# lcd_booster_mk2.net
KiCad netlist of a schematic drawn in EAGLE
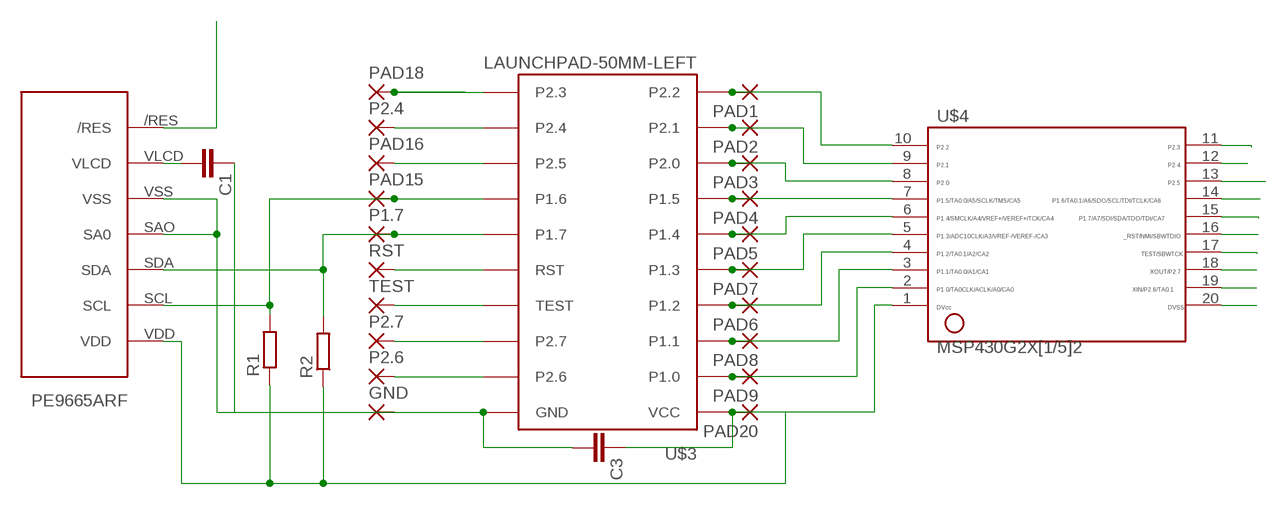
[diagram p0: schematic, sheet 1]

(export (version "E")
  (design (tool "Eeschema 10.0.6"))
  (components
    (comp (ref "C1")
      (value "C-EUC1206")
      (footprint "eagle-import:C1206")
      (libsource (lib "eagle-import") (part "C-EUC1206"))
    )
    (comp (ref "C3")
      (value "C-EUC1206")
      (footprint "eagle-import:C1206")
      (libsource (lib "eagle-import") (part "C-EUC1206"))
    )
    (comp (ref "GND")
      (value "1,6/0,9")
      (footprint "eagle-import:1,6_0,9")
      (libsource (lib "eagle-import") (part "1,6/0,9"))
    )
    (comp (ref "P1.7")
      (value "1,6/0,9")
      (footprint "eagle-import:1,6_0,9")
      (libsource (lib "eagle-import") (part "1,6/0,9"))
    )
    (comp (ref "P2.4")
      (value "1,6/0,9")
      (footprint "eagle-import:1,6_0,9")
      (libsource (lib "eagle-import") (part "1,6/0,9"))
    )
    (comp (ref "P2.6")
      (value "1,6/0,9")
      (footprint "eagle-import:1,6_0,9")
      (libsource (lib "eagle-import") (part "1,6/0,9"))
    )
    (comp (ref "P2.7")
      (value "1,6/0,9")
      (footprint "eagle-import:1,6_0,9")
      (libsource (lib "eagle-import") (part "1,6/0,9"))
    )
    (comp (ref "PAD1")
      (value "1,6/0,9")
      (footprint "eagle-import:1,6_0,9")
      (libsource (lib "eagle-import") (part "1,6/0,9"))
    )
    (comp (ref "PAD2")
      (value "1,6/0,9")
      (footprint "eagle-import:1,6_0,9")
      (libsource (lib "eagle-import") (part "1,6/0,9"))
    )
    (comp (ref "PAD3")
      (value "1,6/0,9")
      (footprint "eagle-import:1,6_0,9")
      (libsource (lib "eagle-import") (part "1,6/0,9"))
    )
    (comp (ref "PAD4")
      (value "1,6/0,9")
      (footprint "eagle-import:1,6_0,9")
      (libsource (lib "eagle-import") (part "1,6/0,9"))
    )
    (comp (ref "PAD5")
      (value "1,6/0,9")
      (footprint "eagle-import:1,6_0,9")
      (libsource (lib "eagle-import") (part "1,6/0,9"))
    )
    (comp (ref "PAD6")
      (value "1,6/0,9")
      (footprint "eagle-import:1,6_0,9")
      (libsource (lib "eagle-import") (part "1,6/0,9"))
    )
    (comp (ref "PAD7")
      (value "1,6/0,9")
      (footprint "eagle-import:1,6_0,9")
      (libsource (lib "eagle-import") (part "1,6/0,9"))
    )
    (comp (ref "PAD8")
      (value "1,6/0,9")
      (footprint "eagle-import:1,6_0,9")
      (libsource (lib "eagle-import") (part "1,6/0,9"))
    )
    (comp (ref "PAD9")
      (value "1,6/0,9")
      (footprint "eagle-import:1,6_0,9")
      (libsource (lib "eagle-import") (part "1,6/0,9"))
    )
    (comp (ref "PAD15")
      (value "1,6/0,9")
      (footprint "eagle-import:1,6_0,9")
      (libsource (lib "eagle-import") (part "1,6/0,9"))
    )
    (comp (ref "PAD16")
      (value "1,6/0,9")
      (footprint "eagle-import:1,6_0,9")
      (libsource (lib "eagle-import") (part "1,6/0,9"))
    )
    (comp (ref "PAD18")
      (value "1,6/0,9")
      (footprint "eagle-import:1,6_0,9")
      (libsource (lib "eagle-import") (part "1,6/0,9"))
    )
    (comp (ref "PAD20")
      (value "1,6/0,9")
      (footprint "eagle-import:1,6_0,9")
      (libsource (lib "eagle-import") (part "1,6/0,9"))
    )
    (comp (ref "R1")
      (value "R-EU_M1206")
      (footprint "eagle-import:M1206")
      (libsource (lib "eagle-import") (part "R-EU_M1206"))
    )
    (comp (ref "R2")
      (value "R-EU_M1206")
      (footprint "eagle-import:M1206")
      (libsource (lib "eagle-import") (part "R-EU_M1206"))
    )
    (comp (ref "RST")
      (value "1,6/0,9")
      (footprint "eagle-import:1,6_0,9")
      (libsource (lib "eagle-import") (part "1,6/0,9"))
    )
    (comp (ref "TEST")
      (value "1,6/0,9")
      (footprint "eagle-import:1,6_0,9")
      (libsource (lib "eagle-import") (part "1,6/0,9"))
    )
    (comp (ref "U$2")
      (value "PE9665ARF")
      (footprint "eagle-import:PE9665ARF")
      (libsource (lib "eagle-import") (part "PE9665ARF"))
    )
    (comp (ref "U$3")
      (value "LAUNCHPAD-50MM-LEFT")
      (footprint "eagle-import:LAUNCHPAD-50MM-LEFT")
      (libsource (lib "eagle-import") (part "LAUNCHPAD-50MM-LEFT"))
    )
    (comp (ref "U$4")
      (value "G2X[1/5]2---PW20")
      (footprint "eagle-import:PW20")
      (libsource (lib "eagle-import") (part "G2X[1/5]2---PW20"))
    )
  )
  (nets
    (net (code "1") (name "/GND") (class "Default")
      (node (ref "C1") (pin "1") (pinfunction "1_1") (pintype "passive"))
      (node (ref "C3") (pin "2") (pinfunction "2_2") (pintype "passive"))
      (node (ref "GND") (pin "1") (pinfunction "P_1") (pintype "passive"))
      (node (ref "U$2") (pin "SAO") (pinfunction "SA0_SAO") (pintype "bidirectional"))
      (node (ref "U$2") (pin "VSS") (pinfunction "VSS_VSS") (pintype "power_in"))
      (node (ref "U$3") (pin "GND") (pinfunction "GND_GND") (pintype "power_in"))
      (node (ref "U$4") (pin "20") (pinfunction "20_20") (pintype "bidirectional"))
    )
    (net (code "2") (name "/P1.6") (class "Default")
      (node (ref "PAD15") (pin "1") (pinfunction "P_1") (pintype "passive"))
      (node (ref "R1") (pin "2") (pinfunction "2_2") (pintype "passive"))
      (node (ref "U$2") (pin "SCL") (pinfunction "SCL_SCL") (pintype "bidirectional"))
      (node (ref "U$3") (pin "P1.6") (pinfunction "P1.6_P1.6") (pintype "bidirectional"))
      (node (ref "U$4") (pin "14") (pinfunction "14_14") (pintype "bidirectional"))
    )
    (net (code "3") (name "/P1.7") (class "Default")
      (node (ref "P1.7") (pin "1") (pinfunction "P_1") (pintype "passive"))
      (node (ref "R2") (pin "2") (pinfunction "2_2") (pintype "passive"))
      (node (ref "U$2") (pin "SDA") (pinfunction "SDA_SDA") (pintype "bidirectional"))
      (node (ref "U$3") (pin "P1.7") (pinfunction "P1.7_P1.7") (pintype "bidirectional"))
      (node (ref "U$4") (pin "15") (pinfunction "15_15") (pintype "bidirectional"))
    )
    (net (code "4") (name "/P2.3") (class "Default")
      (node (ref "PAD18") (pin "1") (pinfunction "P_1") (pintype "passive"))
      (node (ref "U$3") (pin "P2.3") (pinfunction "P2.3_P2.3") (pintype "bidirectional"))
      (node (ref "U$4") (pin "11") (pinfunction "11_11") (pintype "bidirectional"))
    )
    (net (code "5") (name "/P2.4") (class "Default")
      (node (ref "P2.4") (pin "1") (pinfunction "P_1") (pintype "passive"))
      (node (ref "U$3") (pin "P2.4") (pinfunction "P2.4_P2.4") (pintype "bidirectional"))
      (node (ref "U$4") (pin "12") (pinfunction "12_12") (pintype "bidirectional"))
    )
    (net (code "6") (name "/P2.5") (class "Default")
      (node (ref "PAD16") (pin "1") (pinfunction "P_1") (pintype "passive"))
      (node (ref "U$3") (pin "P2.5") (pinfunction "P2.5_P2.5") (pintype "bidirectional"))
      (node (ref "U$4") (pin "13") (pinfunction "13_13") (pintype "bidirectional"))
    )
    (net (code "7") (name "/P2.6") (class "Default")
      (node (ref "P2.6") (pin "1") (pinfunction "P_1") (pintype "passive"))
      (node (ref "U$3") (pin "P2.6") (pinfunction "P2.6_P2.6") (pintype "bidirectional"))
      (node (ref "U$4") (pin "19") (pinfunction "19_19") (pintype "bidirectional"))
    )
    (net (code "8") (name "/P2.7") (class "Default")
      (node (ref "P2.7") (pin "1") (pinfunction "P_1") (pintype "passive"))
      (node (ref "U$3") (pin "P2.7") (pinfunction "P2.7_P2.7") (pintype "bidirectional"))
      (node (ref "U$4") (pin "18") (pinfunction "18_18") (pintype "bidirectional"))
    )
    (net (code "9") (name "/RST") (class "Default")
      (node (ref "RST") (pin "1") (pinfunction "P_1") (pintype "passive"))
      (node (ref "U$3") (pin "RST") (pinfunction "RST_RST") (pintype "bidirectional"))
      (node (ref "U$4") (pin "16") (pinfunction "16_16") (pintype "bidirectional"))
    )
    (net (code "10") (name "/TEST") (class "Default")
      (node (ref "TEST") (pin "1") (pinfunction "P_1") (pintype "passive"))
      (node (ref "U$3") (pin "TEST") (pinfunction "TEST_TEST") (pintype "bidirectional"))
      (node (ref "U$4") (pin "17") (pinfunction "17_17") (pintype "bidirectional"))
    )
    (net (code "11") (name "Net-(C1-Pad2)") (class "Default")
      (node (ref "C1") (pin "2") (pinfunction "2_2") (pintype "passive"))
      (node (ref "U$2") (pin "VLCD") (pinfunction "VLCD_VLCD") (pintype "bidirectional"))
    )
    (net (code "12") (name "Net-(PAD1-P)") (class "Default")
      (node (ref "PAD1") (pin "1") (pinfunction "P_1") (pintype "passive"))
      (node (ref "U$3") (pin "P2.2") (pinfunction "P2.2_P2.2") (pintype "bidirectional"))
      (node (ref "U$4") (pin "10") (pinfunction "10_10") (pintype "bidirectional"))
    )
    (net (code "13") (name "Net-(PAD2-P)") (class "Default")
      (node (ref "PAD2") (pin "1") (pinfunction "P_1") (pintype "passive"))
      (node (ref "U$3") (pin "P2.1") (pinfunction "P2.1_P2.1") (pintype "bidirectional"))
      (node (ref "U$4") (pin "9") (pinfunction "9_9") (pintype "bidirectional"))
    )
    (net (code "14") (name "Net-(PAD3-P)") (class "Default")
      (node (ref "PAD3") (pin "1") (pinfunction "P_1") (pintype "passive"))
      (node (ref "U$3") (pin "P2.0") (pinfunction "P2.0_P2.0") (pintype "bidirectional"))
      (node (ref "U$4") (pin "8") (pinfunction "8_8") (pintype "bidirectional"))
    )
    (net (code "15") (name "Net-(PAD4-P)") (class "Default")
      (node (ref "PAD4") (pin "1") (pinfunction "P_1") (pintype "passive"))
      (node (ref "U$3") (pin "P1.5") (pinfunction "P1.5_P1.5") (pintype "bidirectional"))
      (node (ref "U$4") (pin "7") (pinfunction "7_7") (pintype "bidirectional"))
    )
    (net (code "16") (name "Net-(PAD5-P)") (class "Default")
      (node (ref "PAD5") (pin "1") (pinfunction "P_1") (pintype "passive"))
      (node (ref "U$3") (pin "P1.4") (pinfunction "P1.4_P1.4") (pintype "bidirectional"))
      (node (ref "U$4") (pin "6") (pinfunction "6_6") (pintype "bidirectional"))
    )
    (net (code "17") (name "Net-(PAD6-P)") (class "Default")
      (node (ref "PAD6") (pin "1") (pinfunction "P_1") (pintype "passive"))
      (node (ref "U$3") (pin "P1.2") (pinfunction "P1.2_P1.2") (pintype "bidirectional"))
      (node (ref "U$4") (pin "4") (pinfunction "4_4") (pintype "bidirectional"))
    )
    (net (code "18") (name "Net-(PAD7-P)") (class "Default")
      (node (ref "PAD7") (pin "1") (pinfunction "P_1") (pintype "passive"))
      (node (ref "U$3") (pin "P1.3") (pinfunction "P1.3_P1.3") (pintype "bidirectional"))
      (node (ref "U$4") (pin "5") (pinfunction "5_5") (pintype "bidirectional"))
    )
    (net (code "19") (name "Net-(PAD8-P)") (class "Default")
      (node (ref "PAD8") (pin "1") (pinfunction "P_1") (pintype "passive"))
      (node (ref "U$3") (pin "P1.1") (pinfunction "P1.1_P1.1") (pintype "bidirectional"))
      (node (ref "U$4") (pin "3") (pinfunction "3_3") (pintype "bidirectional"))
    )
    (net (code "20") (name "Net-(PAD9-P)") (class "Default")
      (node (ref "PAD9") (pin "1") (pinfunction "P_1") (pintype "passive"))
      (node (ref "U$3") (pin "P1.0") (pinfunction "P1.0_P1.0") (pintype "bidirectional"))
      (node (ref "U$4") (pin "2") (pinfunction "2_2") (pintype "bidirectional"))
    )
    (net (code "21") (name "Net-(PAD20-P)") (class "Default")
      (node (ref "C3") (pin "1") (pinfunction "1_1") (pintype "passive"))
      (node (ref "PAD20") (pin "1") (pinfunction "P_1") (pintype "passive"))
      (node (ref "R1") (pin "1") (pinfunction "1_1") (pintype "passive"))
      (node (ref "R2") (pin "1") (pinfunction "1_1") (pintype "passive"))
      (node (ref "U$2") (pin "VDD") (pinfunction "VDD_VDD") (pintype "power_in"))
      (node (ref "U$3") (pin "VCC") (pinfunction "VCC_VCC") (pintype "power_in"))
      (node (ref "U$4") (pin "1") (pinfunction "1_1") (pintype "bidirectional"))
    )
    (net (code "22") (name "unconnected-(U$2-Pad{slash}RES)") (class "Default")
      (node (ref "U$2") (pin "/RES") (pinfunction "/RES_/RES") (pintype "bidirectional"))
    )
  )
)
